# Connectors.net
KiCad netlist of a schematic drawn in Altium Designer
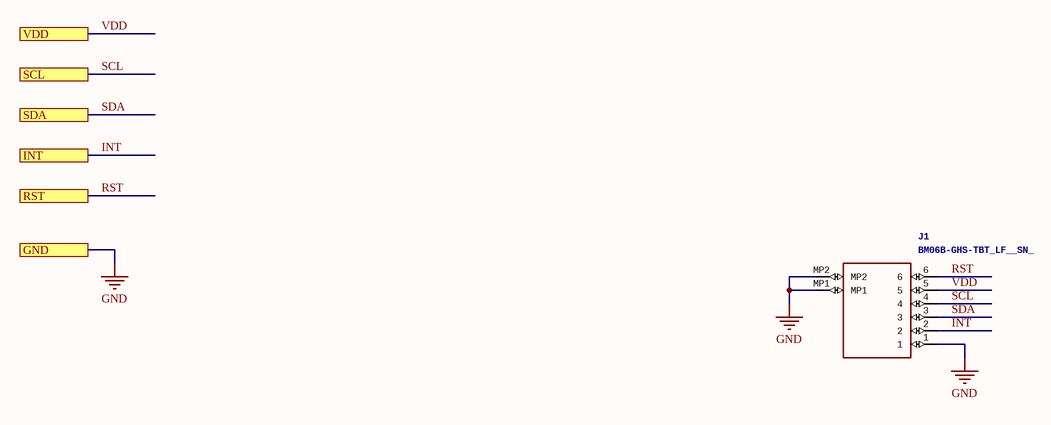
[diagram p0: Connectors.SchDoc]

(export (version "E")
  (design (tool "Eeschema 10.0.6"))
  (components
    (comp (ref "J1")
      (value "BM06B-GHS-TBT_LF__SN_")
      (footprint "BM06BGHSTBTLFSN")
      (description "BM06B Series 6 Position 1.25 mm Pitch Surface Mount Top Entry Shrouded Header   Source:  Datasheet")
      (fields (field (name "MANUFACTURER_PART_NUMBER") "BM06B-GHS-TBT(LF)(SN)"))
      (libsource (lib "FDS") (part "BM06B-GHS-TBT_LF__SN_"))
    )
  )
  (nets
    (net (code "1") (name "/INT") (class "Default")
      (node (ref "J1") (pin "2") (pinfunction "2_2") (pintype "bidirectional"))
    )
    (net (code "2") (name "/RST") (class "Default")
      (node (ref "J1") (pin "6") (pinfunction "6_6") (pintype "bidirectional"))
    )
    (net (code "3") (name "/SCL") (class "Default")
      (node (ref "J1") (pin "4") (pinfunction "4_4") (pintype "bidirectional"))
    )
    (net (code "4") (name "/SDA") (class "Default")
      (node (ref "J1") (pin "3") (pinfunction "3_3") (pintype "bidirectional"))
    )
    (net (code "5") (name "/VDD") (class "Default")
      (node (ref "J1") (pin "5") (pinfunction "5_5") (pintype "bidirectional"))
    )
    (net (code "6") (name "GND") (class "Default")
      (node (ref "J1") (pin "1") (pinfunction "1_1") (pintype "bidirectional"))
      (node (ref "J1") (pin "MP1") (pinfunction "MP1_MP1") (pintype "bidirectional"))
      (node (ref "J1") (pin "MP2") (pinfunction "MP2_MP2") (pintype "bidirectional"))
    )
  )
)
